# MCU089B_F280025C_Device.net
KiCad netlist of a schematic drawn in Altium Designer
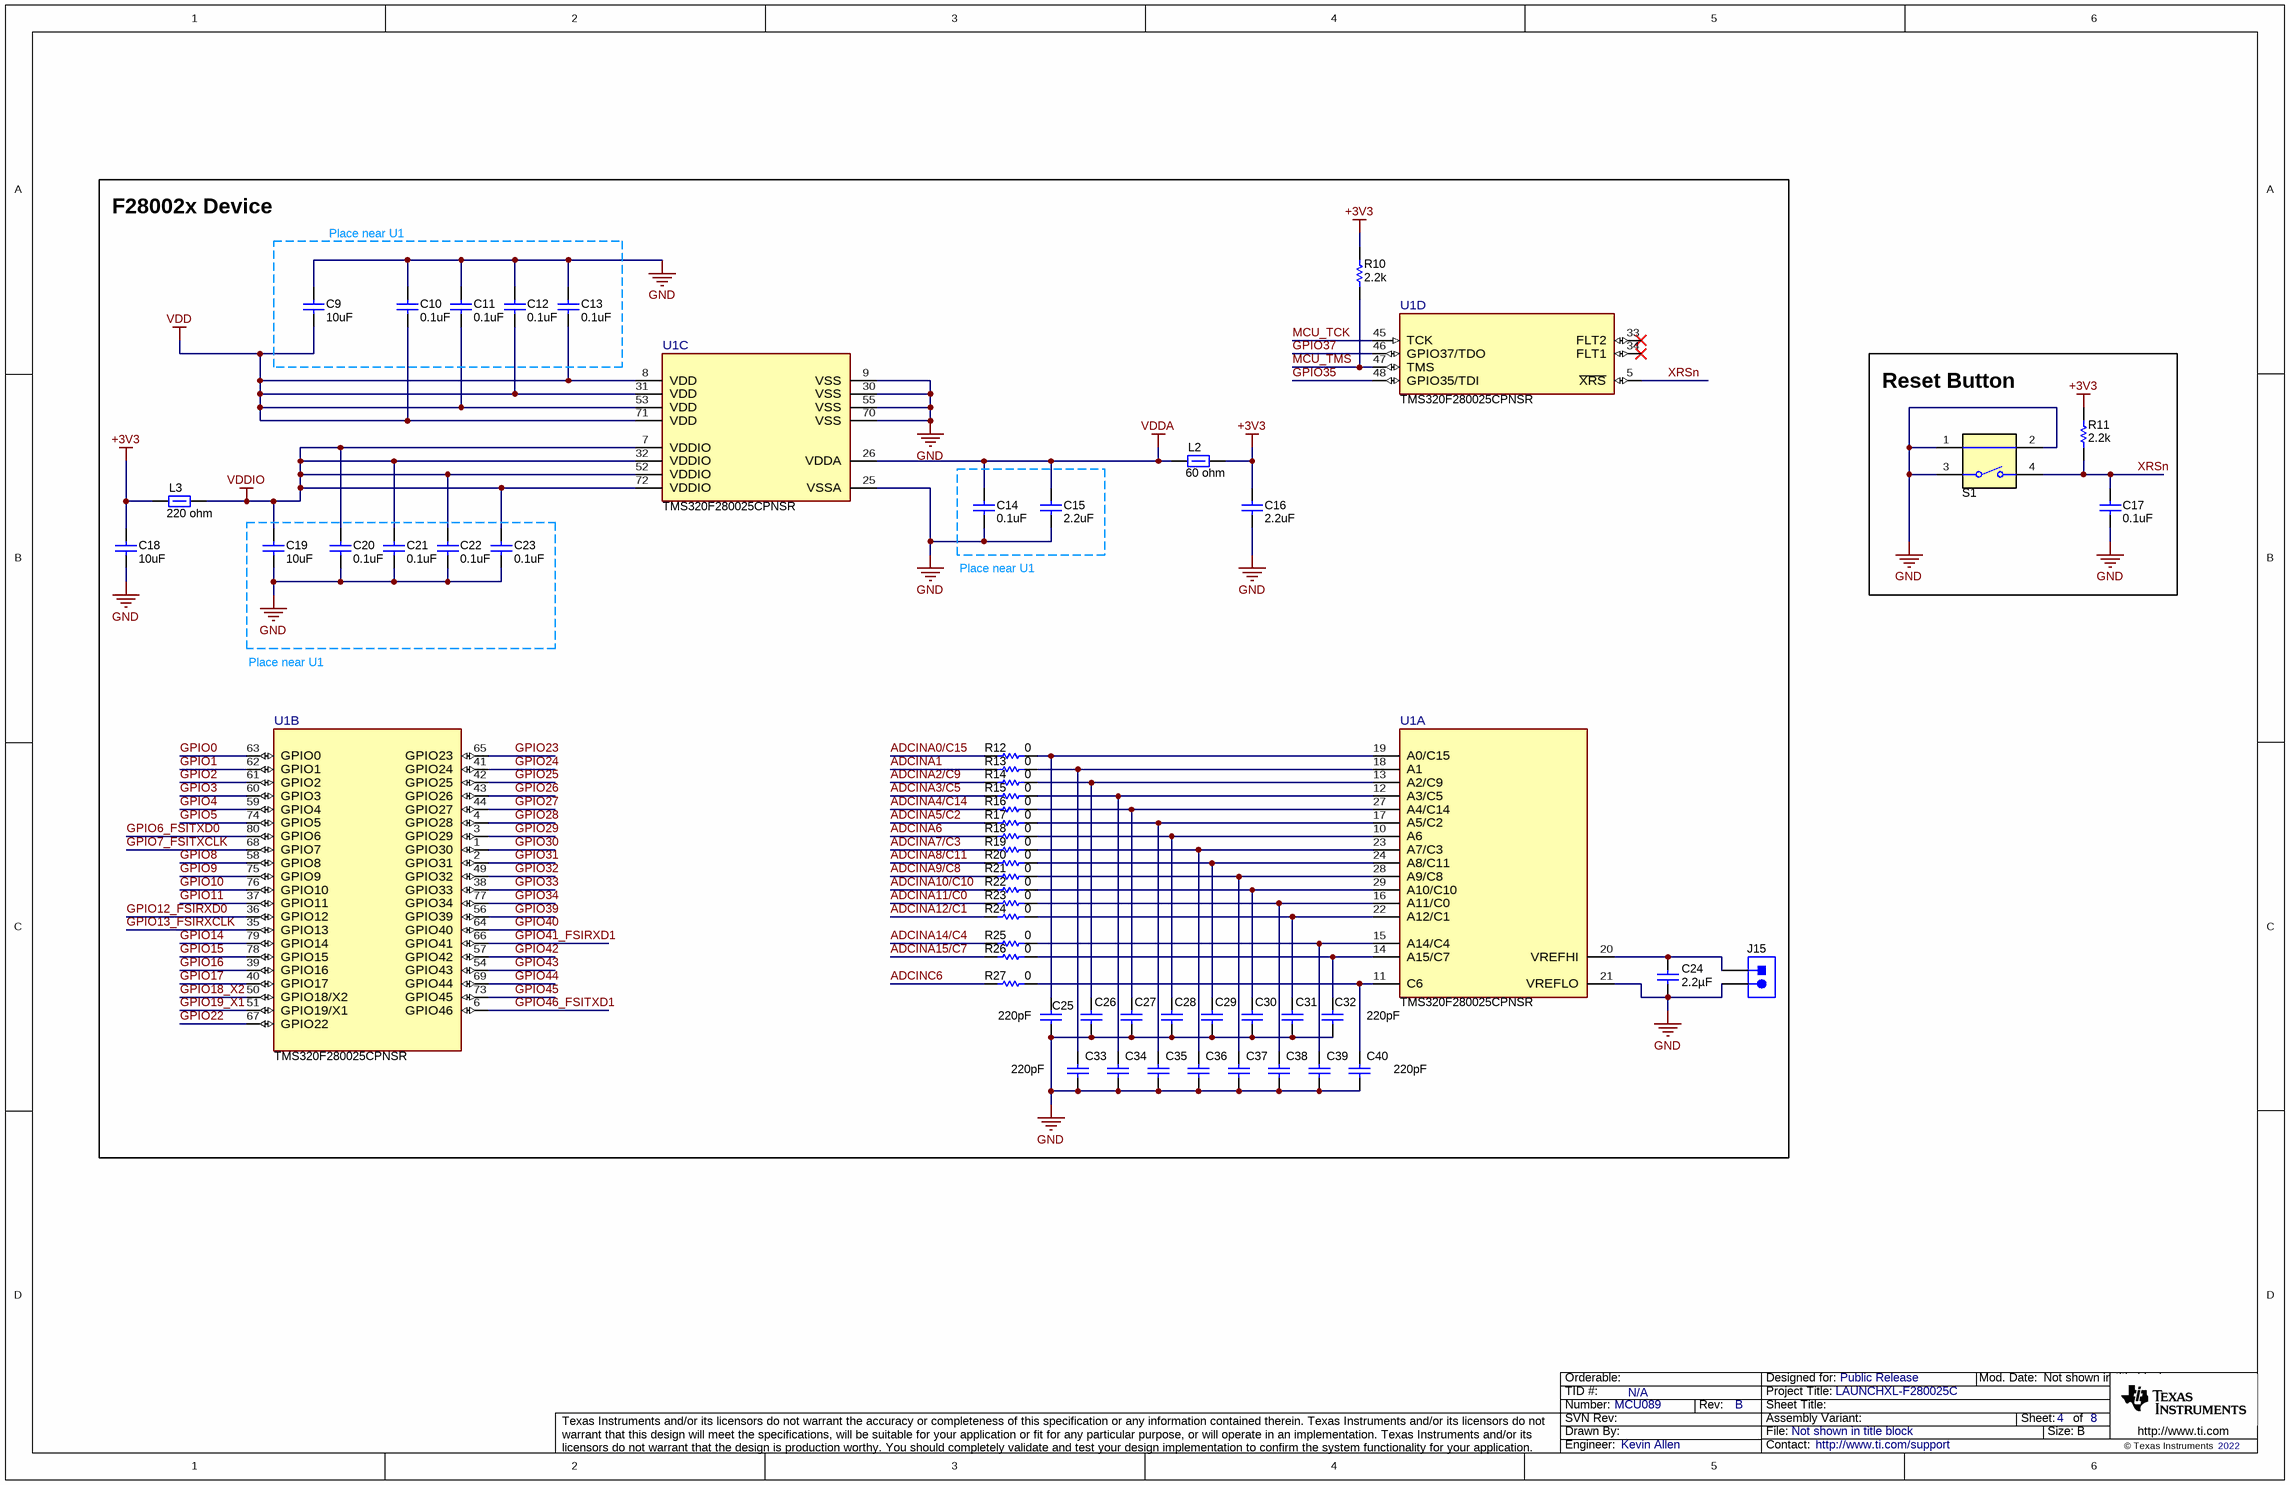
[diagram p0: MCU089B_F280025C_Device.SchDoc]

(export (version "E")
  (design (tool "Eeschema 10.0.6"))
  (components
    (comp (ref "C9")
      (value "GRM188R61A106ME69D")
      (footprint "0603")
      (description "CAP, CERM, 10 uF, 10 V, +/- 20%, X5R, 0603")
      (fields
        (field (name "VALUEDISPLAYED") "10uF")
        (field (name "MANUFACTURER") "MuRata")
        (field (name "PUBLISHER") "Texas Instruments")
      )
      (libsource (lib "Altium Vault - TI") (part "Capacitor"))
    )
    (comp (ref "C10")
      (value "GRM155R71A104KA01D")
      (footprint "0402")
      (description "CAP, CERM, 0.1 uF, 10 V, +/- 10%, X7R, 0402")
      (fields
        (field (name "VALUEDISPLAYED") "0.1uF")
        (field (name "MANUFACTURER") "MuRata")
        (field (name "PUBLISHER") "Texas Instruments")
      )
      (libsource (lib "Altium Vault - TI") (part "Capacitor"))
    )
    (comp (ref "C11")
      (value "GRM155R71A104KA01D")
      (footprint "0402")
      (description "CAP, CERM, 0.1 uF, 10 V, +/- 10%, X7R, 0402")
      (fields
        (field (name "VALUEDISPLAYED") "0.1uF")
        (field (name "MANUFACTURER") "MuRata")
        (field (name "PUBLISHER") "Texas Instruments")
      )
      (libsource (lib "Altium Vault - TI") (part "Capacitor"))
    )
    (comp (ref "C12")
      (value "GRM155R71A104KA01D")
      (footprint "0402")
      (description "CAP, CERM, 0.1 uF, 10 V, +/- 10%, X7R, 0402")
      (fields
        (field (name "VALUEDISPLAYED") "0.1uF")
        (field (name "MANUFACTURER") "MuRata")
        (field (name "PUBLISHER") "Texas Instruments")
      )
      (libsource (lib "Altium Vault - TI") (part "Capacitor"))
    )
    (comp (ref "C13")
      (value "GRM155R71A104KA01D")
      (footprint "0402")
      (description "CAP, CERM, 0.1 uF, 10 V, +/- 10%, X7R, 0402")
      (fields
        (field (name "VALUEDISPLAYED") "0.1uF")
        (field (name "MANUFACTURER") "MuRata")
        (field (name "PUBLISHER") "Texas Instruments")
      )
      (libsource (lib "Altium Vault - TI") (part "Capacitor"))
    )
    (comp (ref "C14")
      (value "GRM155R71A104KA01D")
      (footprint "0402")
      (description "CAP, CERM, 0.1 uF, 10 V, +/- 10%, X7R, 0402")
      (fields
        (field (name "VALUEDISPLAYED") "0.1uF")
        (field (name "MANUFACTURER") "MuRata")
        (field (name "PUBLISHER") "Texas Instruments")
      )
      (libsource (lib "Altium Vault - TI") (part "Capacitor"))
    )
    (comp (ref "C15")
      (value "GRM188R61A225KE34D")
      (footprint "0603")
      (description "CAP, CERM, 2.2 uF, 10 V, +/- 10%, X5R, 0603")
      (fields
        (field (name "VALUEDISPLAYED") "2.2uF")
        (field (name "MANUFACTURER") "MuRata")
        (field (name "PUBLISHER") "Texas Instruments")
      )
      (libsource (lib "Altium Vault - TI") (part "Capacitor"))
    )
    (comp (ref "C16")
      (value "GRM188R61A225KE34D")
      (footprint "0603")
      (description "CAP, CERM, 2.2 uF, 10 V, +/- 10%, X5R, 0603")
      (fields
        (field (name "VALUEDISPLAYED") "2.2uF")
        (field (name "MANUFACTURER") "MuRata")
        (field (name "PUBLISHER") "Texas Instruments")
      )
      (libsource (lib "Altium Vault - TI") (part "Capacitor"))
    )
    (comp (ref "C17")
      (value "GRM155R71A104KA01D")
      (footprint "0402")
      (description "CAP, CERM, 0.1 uF, 10 V, +/- 10%, X7R, 0402")
      (fields
        (field (name "VALUEDISPLAYED") "0.1uF")
        (field (name "MANUFACTURER") "MuRata")
        (field (name "PUBLISHER") "Texas Instruments")
      )
      (libsource (lib "Altium Vault - TI") (part "Capacitor"))
    )
    (comp (ref "C18")
      (value "GRM188R61A106ME69D")
      (footprint "0603")
      (description "CAP, CERM, 10 uF, 10 V, +/- 20%, X5R, 0603")
      (fields
        (field (name "VALUEDISPLAYED") "10uF")
        (field (name "MANUFACTURER") "MuRata")
        (field (name "PUBLISHER") "Texas Instruments")
      )
      (libsource (lib "Altium Vault - TI") (part "Capacitor"))
    )
    (comp (ref "C19")
      (value "GRM188R61A106ME69D")
      (footprint "0603")
      (description "CAP, CERM, 10 uF, 10 V, +/- 20%, X5R, 0603")
      (fields
        (field (name "VALUEDISPLAYED") "10uF")
        (field (name "MANUFACTURER") "MuRata")
        (field (name "PUBLISHER") "Texas Instruments")
      )
      (libsource (lib "Altium Vault - TI") (part "Capacitor"))
    )
    (comp (ref "C20")
      (value "GRM155R71A104KA01D")
      (footprint "0402")
      (description "CAP, CERM, 0.1 uF, 10 V, +/- 10%, X7R, 0402")
      (fields
        (field (name "VALUEDISPLAYED") "0.1uF")
        (field (name "MANUFACTURER") "MuRata")
        (field (name "PUBLISHER") "Texas Instruments")
      )
      (libsource (lib "Altium Vault - TI") (part "Capacitor"))
    )
    (comp (ref "C21")
      (value "GRM155R71A104KA01D")
      (footprint "0402")
      (description "CAP, CERM, 0.1 uF, 10 V, +/- 10%, X7R, 0402")
      (fields
        (field (name "VALUEDISPLAYED") "0.1uF")
        (field (name "MANUFACTURER") "MuRata")
        (field (name "PUBLISHER") "Texas Instruments")
      )
      (libsource (lib "Altium Vault - TI") (part "Capacitor"))
    )
    (comp (ref "C22")
      (value "GRM155R71A104KA01D")
      (footprint "0402")
      (description "CAP, CERM, 0.1 uF, 10 V, +/- 10%, X7R, 0402")
      (fields
        (field (name "VALUEDISPLAYED") "0.1uF")
        (field (name "MANUFACTURER") "MuRata")
        (field (name "PUBLISHER") "Texas Instruments")
      )
      (libsource (lib "Altium Vault - TI") (part "Capacitor"))
    )
    (comp (ref "C23")
      (value "GRM155R71A104KA01D")
      (footprint "0402")
      (description "CAP, CERM, 0.1 uF, 10 V, +/- 10%, X7R, 0402")
      (fields
        (field (name "VALUEDISPLAYED") "0.1uF")
        (field (name "MANUFACTURER") "MuRata")
        (field (name "PUBLISHER") "Texas Instruments")
      )
      (libsource (lib "Altium Vault - TI") (part "Capacitor"))
    )
    (comp (ref "C24")
      (value "GRM188R61A225KE34D")
      (footprint "0603")
      (description "CAP, CERM, 2.2 uF, 10 V, +/- 10%, X5R, 0603")
      (fields
        (field (name "MANUFACTURER") "MuRata")
        (field (name "CAP_F") "2.2µF")
        (field (name "PUBLISHER") "Texas Instruments")
      )
      (libsource (lib "Altium Vault - TI") (part "Capacitor"))
    )
    (comp (ref "C25")
      (value "C1005C0G1H221F050BA")
      (footprint "0402")
      (description "CAP, CERM, 220 pF, 50 V, +/- 1%, C0G/NP0, 0402")
      (fields
        (field (name "MANUFACTURER") "TDK")
        (field (name "CAP_F") "220pF")
        (field (name "PUBLISHER") "Texas Instruments")
      )
      (libsource (lib "Altium Vault - TI") (part "Capacitor"))
    )
    (comp (ref "C26")
      (value "C1005C0G1H221F050BA")
      (footprint "0402")
      (description "CAP, CERM, 220 pF, 50 V, +/- 1%, C0G/NP0, 0402")
      (fields (field (name "MANUFACTURER") "TDK") (field (name "PUBLISHER") "Texas Instruments"))
      (libsource (lib "Altium Vault - TI") (part "Capacitor"))
    )
    (comp (ref "C27")
      (value "C1005C0G1H221F050BA")
      (footprint "0402")
      (description "CAP, CERM, 220 pF, 50 V, +/- 1%, C0G/NP0, 0402")
      (fields (field (name "MANUFACTURER") "TDK") (field (name "PUBLISHER") "Texas Instruments"))
      (libsource (lib "Altium Vault - TI") (part "Capacitor"))
    )
    (comp (ref "C28")
      (value "C1005C0G1H221F050BA")
      (footprint "0402")
      (description "CAP, CERM, 220 pF, 50 V, +/- 1%, C0G/NP0, 0402")
      (fields (field (name "MANUFACTURER") "TDK") (field (name "PUBLISHER") "Texas Instruments"))
      (libsource (lib "Altium Vault - TI") (part "Capacitor"))
    )
    (comp (ref "C29")
      (value "C1005C0G1H221F050BA")
      (footprint "0402")
      (description "CAP, CERM, 220 pF, 50 V, +/- 1%, C0G/NP0, 0402")
      (fields (field (name "MANUFACTURER") "TDK") (field (name "PUBLISHER") "Texas Instruments"))
      (libsource (lib "Altium Vault - TI") (part "Capacitor"))
    )
    (comp (ref "C30")
      (value "C1005C0G1H221F050BA")
      (footprint "0402")
      (description "CAP, CERM, 220 pF, 50 V, +/- 1%, C0G/NP0, 0402")
      (fields (field (name "MANUFACTURER") "TDK") (field (name "PUBLISHER") "Texas Instruments"))
      (libsource (lib "Altium Vault - TI") (part "Capacitor"))
    )
    (comp (ref "C31")
      (value "C1005C0G1H221F050BA")
      (footprint "0402")
      (description "CAP, CERM, 220 pF, 50 V, +/- 1%, C0G/NP0, 0402")
      (fields (field (name "MANUFACTURER") "TDK") (field (name "PUBLISHER") "Texas Instruments"))
      (libsource (lib "Altium Vault - TI") (part "Capacitor"))
    )
    (comp (ref "C32")
      (value "C1005C0G1H221F050BA")
      (footprint "0402")
      (description "CAP, CERM, 220 pF, 50 V, +/- 1%, C0G/NP0, 0402")
      (fields
        (field (name "MANUFACTURER") "TDK")
        (field (name "CAP_F") "220pF")
        (field (name "PUBLISHER") "Texas Instruments")
      )
      (libsource (lib "Altium Vault - TI") (part "Capacitor"))
    )
    (comp (ref "C33")
      (value "C1005C0G1H221F050BA")
      (footprint "0402")
      (description "CAP, CERM, 220 pF, 50 V, +/- 1%, C0G/NP0, 0402")
      (fields
        (field (name "MANUFACTURER") "TDK")
        (field (name "CAP_F") "220pF")
        (field (name "PUBLISHER") "Texas Instruments")
      )
      (libsource (lib "Altium Vault - TI") (part "Capacitor"))
    )
    (comp (ref "C34")
      (value "C1005C0G1H221F050BA")
      (footprint "0402")
      (description "CAP, CERM, 220 pF, 50 V, +/- 1%, C0G/NP0, 0402")
      (fields (field (name "MANUFACTURER") "TDK") (field (name "PUBLISHER") "Texas Instruments"))
      (libsource (lib "Altium Vault - TI") (part "Capacitor"))
    )
    (comp (ref "C35")
      (value "C1005C0G1H221F050BA")
      (footprint "0402")
      (description "CAP, CERM, 220 pF, 50 V, +/- 1%, C0G/NP0, 0402")
      (fields (field (name "MANUFACTURER") "TDK") (field (name "PUBLISHER") "Texas Instruments"))
      (libsource (lib "Altium Vault - TI") (part "Capacitor"))
    )
    (comp (ref "C36")
      (value "C1005C0G1H221F050BA")
      (footprint "0402")
      (description "CAP, CERM, 220 pF, 50 V, +/- 1%, C0G/NP0, 0402")
      (fields (field (name "MANUFACTURER") "TDK") (field (name "PUBLISHER") "Texas Instruments"))
      (libsource (lib "Altium Vault - TI") (part "Capacitor"))
    )
    (comp (ref "C37")
      (value "C1005C0G1H221F050BA")
      (footprint "0402")
      (description "CAP, CERM, 220 pF, 50 V, +/- 1%, C0G/NP0, 0402")
      (fields (field (name "MANUFACTURER") "TDK") (field (name "PUBLISHER") "Texas Instruments"))
      (libsource (lib "Altium Vault - TI") (part "Capacitor"))
    )
    (comp (ref "C38")
      (value "C1005C0G1H221F050BA")
      (footprint "0402")
      (description "CAP, CERM, 220 pF, 50 V, +/- 1%, C0G/NP0, 0402")
      (fields (field (name "MANUFACTURER") "TDK") (field (name "PUBLISHER") "Texas Instruments"))
      (libsource (lib "Altium Vault - TI") (part "Capacitor"))
    )
    (comp (ref "C39")
      (value "C1005C0G1H221F050BA")
      (footprint "0402")
      (description "CAP, CERM, 220 pF, 50 V, +/- 1%, C0G/NP0, 0402")
      (fields (field (name "MANUFACTURER") "TDK") (field (name "PUBLISHER") "Texas Instruments"))
      (libsource (lib "Altium Vault - TI") (part "Capacitor"))
    )
    (comp (ref "C40")
      (value "C1005C0G1H221F050BA")
      (footprint "0402")
      (description "CAP, CERM, 220 pF, 50 V, +/- 1%, C0G/NP0, 0402")
      (fields
        (field (name "MANUFACTURER") "TDK")
        (field (name "CAP_F") "220pF")
        (field (name "PUBLISHER") "Texas Instruments")
      )
      (libsource (lib "Altium Vault - TI") (part "Capacitor"))
    )
    (comp (ref "J15")
      (value "61300211121")
      (footprint "WURTH_61300211121")
      (description "Header, 2.54 mm, 2x1, Gold, TH")
      (fields (field (name "MANUFACTURER") "Wurth Elektronik") (field (name "PUBLISHER") "Texas Instruments"))
      (libsource (lib "Altium Vault - TI") (part "CMP-0054794-1"))
    )
    (comp (ref "L2")
      (value "60 ohm")
      (footprint "0805_HV")
      (description "Ferrite Bead, 60 ohm @ 100 MHz, 3 A, 0805")
      (fields
        (field (name "MANUFACTURER") "Wurth Elektronik")
        (field (name "PARTNUMBER") "742792063")
        (field (name "PUBLISHER") "Texas Instruments")
      )
      (libsource (lib "Altium Vault - TI") (part "Ferrite_Bead"))
    )
    (comp (ref "L3")
      (value "742792022")
      (footprint "0805_HV")
      (description "Ferrite Bead, 220 ohm @ 100 MHz, 2 A, 0805")
      (fields
        (field (name "MANUFACTURER") "Wurth Elektronik")
        (field (name "VALUEDISPLAYED") "220 ohm")
        (field (name "PUBLISHER") "Texas Instruments")
      )
      (libsource (lib "Altium Vault - TI") (part "Ferrite_Bead"))
    )
    (comp (ref "R10")
      (value "CRCW04022K20JNED")
      (footprint "0402")
      (description "RES, 2.2 k, 5%, 0.063 W, AEC-Q200 Grade 0, 0402")
      (fields (field (name "VALUEDISPLAYED") "2.2k") (field (name "MANUFACTURER") "Vishay-Dale"))
      (libsource (lib "Altium Vault - TI") (part "Resistor"))
    )
    (comp (ref "R11")
      (value "CRCW04022K20JNED")
      (footprint "0402")
      (description "RES, 2.2 k, 5%, 0.063 W, AEC-Q200 Grade 0, 0402")
      (fields (field (name "VALUEDISPLAYED") "2.2k") (field (name "MANUFACTURER") "Vishay-Dale"))
      (libsource (lib "Altium Vault - TI") (part "Resistor"))
    )
    (comp (ref "R12")
      (value "ERJ-2GE0R00X")
      (footprint "0402")
      (description "RES, 0, 5%, 0.1 W, AEC-Q200 Grade 0, 0402")
      (fields (field (name "MANUFACTURER") "Panasonic") (field (name "VALUEDISPLAYED") "0"))
      (libsource (lib "Altium Vault - TI") (part "Resistor"))
    )
    (comp (ref "R13")
      (value "ERJ-2GE0R00X")
      (footprint "0402")
      (description "RES, 0, 5%, 0.1 W, AEC-Q200 Grade 0, 0402")
      (fields (field (name "MANUFACTURER") "Panasonic") (field (name "VALUEDISPLAYED") "0"))
      (libsource (lib "Altium Vault - TI") (part "Resistor"))
    )
    (comp (ref "R14")
      (value "ERJ-2GE0R00X")
      (footprint "0402")
      (description "RES, 0, 5%, 0.1 W, AEC-Q200 Grade 0, 0402")
      (fields (field (name "MANUFACTURER") "Panasonic") (field (name "VALUEDISPLAYED") "0"))
      (libsource (lib "Altium Vault - TI") (part "Resistor"))
    )
    (comp (ref "R15")
      (value "ERJ-2GE0R00X")
      (footprint "0402")
      (description "RES, 0, 5%, 0.1 W, AEC-Q200 Grade 0, 0402")
      (fields (field (name "MANUFACTURER") "Panasonic") (field (name "VALUEDISPLAYED") "0"))
      (libsource (lib "Altium Vault - TI") (part "Resistor"))
    )
    (comp (ref "R16")
      (value "ERJ-2GE0R00X")
      (footprint "0402")
      (description "RES, 0, 5%, 0.1 W, AEC-Q200 Grade 0, 0402")
      (fields (field (name "MANUFACTURER") "Panasonic") (field (name "VALUEDISPLAYED") "0"))
      (libsource (lib "Altium Vault - TI") (part "Resistor"))
    )
    (comp (ref "R17")
      (value "ERJ-2GE0R00X")
      (footprint "0402")
      (description "RES, 0, 5%, 0.1 W, AEC-Q200 Grade 0, 0402")
      (fields (field (name "MANUFACTURER") "Panasonic") (field (name "VALUEDISPLAYED") "0"))
      (libsource (lib "Altium Vault - TI") (part "Resistor"))
    )
    (comp (ref "R18")
      (value "ERJ-2GE0R00X")
      (footprint "0402")
      (description "RES, 0, 5%, 0.1 W, AEC-Q200 Grade 0, 0402")
      (fields (field (name "MANUFACTURER") "Panasonic") (field (name "VALUEDISPLAYED") "0"))
      (libsource (lib "Altium Vault - TI") (part "Resistor"))
    )
    (comp (ref "R19")
      (value "ERJ-2GE0R00X")
      (footprint "0402")
      (description "RES, 0, 5%, 0.1 W, AEC-Q200 Grade 0, 0402")
      (fields (field (name "MANUFACTURER") "Panasonic") (field (name "VALUEDISPLAYED") "0"))
      (libsource (lib "Altium Vault - TI") (part "Resistor"))
    )
    (comp (ref "R20")
      (value "ERJ-2GE0R00X")
      (footprint "0402")
      (description "RES, 0, 5%, 0.1 W, AEC-Q200 Grade 0, 0402")
      (fields (field (name "MANUFACTURER") "Panasonic") (field (name "VALUEDISPLAYED") "0"))
      (libsource (lib "Altium Vault - TI") (part "Resistor"))
    )
    (comp (ref "R21")
      (value "ERJ-2GE0R00X")
      (footprint "0402")
      (description "RES, 0, 5%, 0.1 W, AEC-Q200 Grade 0, 0402")
      (fields (field (name "MANUFACTURER") "Panasonic") (field (name "VALUEDISPLAYED") "0"))
      (libsource (lib "Altium Vault - TI") (part "Resistor"))
    )
    (comp (ref "R22")
      (value "ERJ-2GE0R00X")
      (footprint "0402")
      (description "RES, 0, 5%, 0.1 W, AEC-Q200 Grade 0, 0402")
      (fields (field (name "MANUFACTURER") "Panasonic") (field (name "VALUEDISPLAYED") "0"))
      (libsource (lib "Altium Vault - TI") (part "Resistor"))
    )
    (comp (ref "R23")
      (value "ERJ-2GE0R00X")
      (footprint "0402")
      (description "RES, 0, 5%, 0.1 W, AEC-Q200 Grade 0, 0402")
      (fields (field (name "MANUFACTURER") "Panasonic") (field (name "VALUEDISPLAYED") "0"))
      (libsource (lib "Altium Vault - TI") (part "Resistor"))
    )
    (comp (ref "R24")
      (value "ERJ-2GE0R00X")
      (footprint "0402")
      (description "RES, 0, 5%, 0.1 W, AEC-Q200 Grade 0, 0402")
      (fields (field (name "MANUFACTURER") "Panasonic") (field (name "VALUEDISPLAYED") "0"))
      (libsource (lib "Altium Vault - TI") (part "Resistor"))
    )
    (comp (ref "R25")
      (value "ERJ-2GE0R00X")
      (footprint "0402")
      (description "RES, 0, 5%, 0.1 W, AEC-Q200 Grade 0, 0402")
      (fields (field (name "MANUFACTURER") "Panasonic") (field (name "VALUEDISPLAYED") "0"))
      (libsource (lib "Altium Vault - TI") (part "Resistor"))
    )
    (comp (ref "R26")
      (value "ERJ-2GE0R00X")
      (footprint "0402")
      (description "RES, 0, 5%, 0.1 W, AEC-Q200 Grade 0, 0402")
      (fields (field (name "MANUFACTURER") "Panasonic") (field (name "VALUEDISPLAYED") "0"))
      (libsource (lib "Altium Vault - TI") (part "Resistor"))
    )
    (comp (ref "R27")
      (value "ERJ-2GE0R00X")
      (footprint "0402")
      (description "RES, 0, 5%, 0.1 W, AEC-Q200 Grade 0, 0402")
      (fields (field (name "MANUFACTURER") "Panasonic") (field (name "VALUEDISPLAYED") "0"))
      (libsource (lib "Altium Vault - TI") (part "Resistor"))
    )
    (comp (ref "S1")
      (value "1188E-1K2-V-TR")
      (footprint "SW_1188E")
      (description "Switch, SPST, 0.05 A, 12 VDC, SMD")
      (fields (field (name "MANUFACTURER") "Diptronics") (field (name "PUBLISHER") "Texas Instruments"))
      (libsource (lib "Altium Vault - TI") (part "SW_1188E"))
    )
    (comp (ref "U1")
      (value "TMS320F280025CPNSR")
      (footprint "PN0080A-MFG")
      (description "32-bit MCU with 100 MHz, FPU, TMU, 128-KB flash, CLB 80-LQFP -40 to 125")
      (fields
        (field (name "MANUFACTURER") "Texas Instruments")
        (field (name "PARTNUMBER") "TMS320F280025CPNSR")
      )
      (libsource (lib "Altium Vault - TI") (part "SYM-TMS320F280025CPNSR"))
    )
  )
  (nets
    (net (code "1") (name "+3V3") (class "Default")
      (node (ref "C16") (pin "1") (pinfunction "1_1") (pintype "passive"))
      (node (ref "C18") (pin "1") (pinfunction "1_1") (pintype "passive"))
      (node (ref "L2") (pin "2") (pinfunction "2_2") (pintype "passive"))
      (node (ref "L3") (pin "1") (pinfunction "1_1") (pintype "passive"))
      (node (ref "R10") (pin "2") (pinfunction "2_2") (pintype "passive"))
      (node (ref "R11") (pin "2") (pinfunction "2_2") (pintype "passive"))
    )
    (net (code "2") (name "/ADCINA0{slash}C15") (class "Default")
      (node (ref "R12") (pin "1") (pinfunction "1_1") (pintype "passive"))
    )
    (net (code "3") (name "/ADCINA1") (class "Default")
      (node (ref "R13") (pin "1") (pinfunction "1_1") (pintype "passive"))
    )
    (net (code "4") (name "/ADCINA2{slash}C9") (class "Default")
      (node (ref "R14") (pin "1") (pinfunction "1_1") (pintype "passive"))
    )
    (net (code "5") (name "/ADCINA3{slash}C5") (class "Default")
      (node (ref "R15") (pin "1") (pinfunction "1_1") (pintype "passive"))
    )
    (net (code "6") (name "/ADCINA4{slash}C14") (class "Default")
      (node (ref "R16") (pin "1") (pinfunction "1_1") (pintype "passive"))
    )
    (net (code "7") (name "/ADCINA5{slash}C2") (class "Default")
      (node (ref "R17") (pin "1") (pinfunction "1_1") (pintype "passive"))
    )
    (net (code "8") (name "/ADCINA6") (class "Default")
      (node (ref "R18") (pin "1") (pinfunction "1_1") (pintype "passive"))
    )
    (net (code "9") (name "/ADCINA7{slash}C3") (class "Default")
      (node (ref "R19") (pin "1") (pinfunction "1_1") (pintype "passive"))
    )
    (net (code "10") (name "/ADCINA8{slash}C11") (class "Default")
      (node (ref "R20") (pin "1") (pinfunction "1_1") (pintype "passive"))
    )
    (net (code "11") (name "/ADCINA9{slash}C8") (class "Default")
      (node (ref "R21") (pin "1") (pinfunction "1_1") (pintype "passive"))
    )
    (net (code "12") (name "/ADCINA10{slash}C10") (class "Default")
      (node (ref "R22") (pin "1") (pinfunction "1_1") (pintype "passive"))
    )
    (net (code "13") (name "/ADCINA11{slash}C0") (class "Default")
      (node (ref "R23") (pin "1") (pinfunction "1_1") (pintype "passive"))
    )
    (net (code "14") (name "/ADCINA12{slash}C1") (class "Default")
      (node (ref "R24") (pin "1") (pinfunction "1_1") (pintype "passive"))
    )
    (net (code "15") (name "/ADCINA14{slash}C4") (class "Default")
      (node (ref "R25") (pin "1") (pinfunction "1_1") (pintype "passive"))
    )
    (net (code "16") (name "/ADCINA15{slash}C7") (class "Default")
      (node (ref "R26") (pin "1") (pinfunction "1_1") (pintype "passive"))
    )
    (net (code "17") (name "/ADCINC6") (class "Default")
      (node (ref "R27") (pin "1") (pinfunction "1_1") (pintype "passive"))
    )
    (net (code "18") (name "/GPIO0") (class "Default")
      (node (ref "U1") (pin "63") (pinfunction "GPIO0_63") (pintype "bidirectional"))
    )
    (net (code "19") (name "/GPIO1") (class "Default")
      (node (ref "U1") (pin "62") (pinfunction "GPIO1_62") (pintype "bidirectional"))
    )
    (net (code "20") (name "/GPIO2") (class "Default")
      (node (ref "U1") (pin "61") (pinfunction "GPIO2_61") (pintype "bidirectional"))
    )
    (net (code "21") (name "/GPIO3") (class "Default")
      (node (ref "U1") (pin "60") (pinfunction "GPIO3_60") (pintype "bidirectional"))
    )
    (net (code "22") (name "/GPIO4") (class "Default")
      (node (ref "U1") (pin "59") (pinfunction "GPIO4_59") (pintype "bidirectional"))
    )
    (net (code "23") (name "/GPIO5") (class "Default")
      (node (ref "U1") (pin "74") (pinfunction "GPIO5_74") (pintype "bidirectional"))
    )
    (net (code "24") (name "/GPIO6_FSITXD0") (class "Default")
      (node (ref "U1") (pin "80") (pinfunction "GPIO6_80") (pintype "bidirectional"))
    )
    (net (code "25") (name "/GPIO7_FSITXCLK") (class "Default")
      (node (ref "U1") (pin "68") (pinfunction "GPIO7_68") (pintype "bidirectional"))
    )
    (net (code "26") (name "/GPIO8") (class "Default")
      (node (ref "U1") (pin "58") (pinfunction "GPIO8_58") (pintype "bidirectional"))
    )
    (net (code "27") (name "/GPIO9") (class "Default")
      (node (ref "U1") (pin "75") (pinfunction "GPIO9_75") (pintype "bidirectional"))
    )
    (net (code "28") (name "/GPIO10") (class "Default")
      (node (ref "U1") (pin "76") (pinfunction "GPIO10_76") (pintype "bidirectional"))
    )
    (net (code "29") (name "/GPIO11") (class "Default")
      (node (ref "U1") (pin "37") (pinfunction "GPIO11_37") (pintype "bidirectional"))
    )
    (net (code "30") (name "/GPIO12_FSIRXD0") (class "Default")
      (node (ref "U1") (pin "36") (pinfunction "GPIO12_36") (pintype "bidirectional"))
    )
    (net (code "31") (name "/GPIO13_FSIRXCLK") (class "Default")
      (node (ref "U1") (pin "35") (pinfunction "GPIO13_35") (pintype "bidirectional"))
    )
    (net (code "32") (name "/GPIO14") (class "Default")
      (node (ref "U1") (pin "79") (pinfunction "GPIO14_79") (pintype "bidirectional"))
    )
    (net (code "33") (name "/GPIO15") (class "Default")
      (node (ref "U1") (pin "78") (pinfunction "GPIO15_78") (pintype "bidirectional"))
    )
    (net (code "34") (name "/GPIO16") (class "Default")
      (node (ref "U1") (pin "39") (pinfunction "GPIO16_39") (pintype "bidirectional"))
    )
    (net (code "35") (name "/GPIO17") (class "Default")
      (node (ref "U1") (pin "40") (pinfunction "GPIO17_40") (pintype "bidirectional"))
    )
    (net (code "36") (name "/GPIO18_X2") (class "Default")
      (node (ref "U1") (pin "50") (pinfunction "GPIO18/X2_50") (pintype "bidirectional"))
    )
    (net (code "37") (name "/GPIO19_X1") (class "Default")
      (node (ref "U1") (pin "51") (pinfunction "GPIO19/X1_51") (pintype "bidirectional"))
    )
    (net (code "38") (name "/GPIO22") (class "Default")
      (node (ref "U1") (pin "67") (pinfunction "GPIO22_67") (pintype "bidirectional"))
    )
    (net (code "39") (name "/GPIO23") (class "Default")
      (node (ref "U1") (pin "65") (pinfunction "GPIO23_65") (pintype "bidirectional"))
    )
    (net (code "40") (name "/GPIO24") (class "Default")
      (node (ref "U1") (pin "41") (pinfunction "GPIO24_41") (pintype "bidirectional"))
    )
    (net (code "41") (name "/GPIO25") (class "Default")
      (node (ref "U1") (pin "42") (pinfunction "GPIO25_42") (pintype "bidirectional"))
    )
    (net (code "42") (name "/GPIO26") (class "Default")
      (node (ref "U1") (pin "43") (pinfunction "GPIO26_43") (pintype "bidirectional"))
    )
    (net (code "43") (name "/GPIO27") (class "Default")
      (node (ref "U1") (pin "44") (pinfunction "GPIO27_44") (pintype "bidirectional"))
    )
    (net (code "44") (name "/GPIO28") (class "Default")
      (node (ref "U1") (pin "4") (pinfunction "GPIO28_4") (pintype "bidirectional"))
    )
    (net (code "45") (name "/GPIO29") (class "Default")
      (node (ref "U1") (pin "3") (pinfunction "GPIO29_3") (pintype "bidirectional"))
    )
    (net (code "46") (name "/GPIO30") (class "Default")
      (node (ref "U1") (pin "1") (pinfunction "GPIO30_1") (pintype "bidirectional"))
    )
    (net (code "47") (name "/GPIO31") (class "Default")
      (node (ref "U1") (pin "2") (pinfunction "GPIO31_2") (pintype "bidirectional"))
    )
    (net (code "48") (name "/GPIO32") (class "Default")
      (node (ref "U1") (pin "49") (pinfunction "GPIO32_49") (pintype "bidirectional"))
    )
    (net (code "49") (name "/GPIO33") (class "Default")
      (node (ref "U1") (pin "38") (pinfunction "GPIO33_38") (pintype "bidirectional"))
    )
    (net (code "50") (name "/GPIO34") (class "Default")
      (node (ref "U1") (pin "77") (pinfunction "GPIO34_77") (pintype "bidirectional"))
    )
    (net (code "51") (name "/GPIO35") (class "Default")
      (node (ref "U1") (pin "48") (pinfunction "GPIO35/TDI_48") (pintype "bidirectional"))
    )
    (net (code "52") (name "/GPIO37") (class "Default")
      (node (ref "U1") (pin "46") (pinfunction "GPIO37/TDO_46") (pintype "bidirectional"))
    )
    (net (code "53") (name "/GPIO39") (class "Default")
      (node (ref "U1") (pin "56") (pinfunction "GPIO39_56") (pintype "bidirectional"))
    )
    (net (code "54") (name "/GPIO40") (class "Default")
      (node (ref "U1") (pin "64") (pinfunction "GPIO40_64") (pintype "bidirectional"))
    )
    (net (code "55") (name "/GPIO41_FSIRXD1") (class "Default")
      (node (ref "U1") (pin "66") (pinfunction "GPIO41_66") (pintype "bidirectional"))
    )
    (net (code "56") (name "/GPIO42") (class "Default")
      (node (ref "U1") (pin "57") (pinfunction "GPIO42_57") (pintype "bidirectional"))
    )
    (net (code "57") (name "/GPIO43") (class "Default")
      (node (ref "U1") (pin "54") (pinfunction "GPIO43_54") (pintype "bidirectional"))
    )
    (net (code "58") (name "/GPIO44") (class "Default")
      (node (ref "U1") (pin "69") (pinfunction "GPIO44_69") (pintype "bidirectional"))
    )
    (net (code "59") (name "/GPIO45") (class "Default")
      (node (ref "U1") (pin "73") (pinfunction "GPIO45_73") (pintype "bidirectional"))
    )
    (net (code "60") (name "/GPIO46_FSITXD1") (class "Default")
      (node (ref "U1") (pin "6") (pinfunction "GPIO46_6") (pintype "bidirectional"))
    )
    (net (code "61") (name "/MCU_TCK") (class "Default")
      (node (ref "U1") (pin "45") (pinfunction "TCK_45") (pintype "input"))
    )
    (net (code "62") (name "/MCU_TMS") (class "Default")
      (node (ref "R10") (pin "1") (pinfunction "1_1") (pintype "passive"))
      (node (ref "U1") (pin "47") (pinfunction "TMS_47") (pintype "bidirectional"))
    )
    (net (code "63") (name "/XRSn") (class "Default")
      (node (ref "C17") (pin "2") (pinfunction "2_2") (pintype "passive"))
      (node (ref "R11") (pin "1") (pinfunction "1_1") (pintype "passive"))
      (node (ref "S1") (pin "4") (pinfunction "4_4") (pintype "passive"))
      (node (ref "U1") (pin "5") (pinfunction "~{XRS}_5") (pintype "bidirectional"))
    )
    (net (code "64") (name "GND") (class "Default")
      (node (ref "C10") (pin "2") (pinfunction "2_2") (pintype "passive"))
      (node (ref "C11") (pin "2") (pinfunction "2_2") (pintype "passive"))
      (node (ref "C12") (pin "2") (pinfunction "2_2") (pintype "passive"))
      (node (ref "C13") (pin "2") (pinfunction "2_2") (pintype "passive"))
      (node (ref "C14") (pin "1") (pinfunction "1_1") (pintype "passive"))
      (node (ref "C15") (pin "2") (pinfunction "2_2") (pintype "passive"))
      (node (ref "C16") (pin "2") (pinfunction "2_2") (pintype "passive"))
      (node (ref "C17") (pin "1") (pinfunction "1_1") (pintype "passive"))
      (node (ref "C18") (pin "2") (pinfunction "2_2") (pintype "passive"))
      (node (ref "C19") (pin "2") (pinfunction "2_2") (pintype "passive"))
      (node (ref "C20") (pin "1") (pinfunction "1_1") (pintype "passive"))
      (node (ref "C21") (pin "1") (pinfunction "1_1") (pintype "passive"))
      (node (ref "C22") (pin "1") (pinfunction "1_1") (pintype "passive"))
      (node (ref "C23") (pin "1") (pinfunction "1_1") (pintype "passive"))
      (node (ref "C24") (pin "2") (pinfunction "2_2") (pintype "passive"))
      (node (ref "C25") (pin "2") (pinfunction "2_2") (pintype "passive"))
      (node (ref "C26") (pin "2") (pinfunction "2_2") (pintype "passive"))
      (node (ref "C27") (pin "2") (pinfunction "2_2") (pintype "passive"))
      (node (ref "C28") (pin "2") (pinfunction "2_2") (pintype "passive"))
      (node (ref "C29") (pin "2") (pinfunction "2_2") (pintype "passive"))
      (node (ref "C30") (pin "2") (pinfunction "2_2") (pintype "passive"))
      (node (ref "C31") (pin "2") (pinfunction "2_2") (pintype "passive"))
      (node (ref "C32") (pin "2") (pinfunction "2_2") (pintype "passive"))
      (node (ref "C33") (pin "2") (pinfunction "2_2") (pintype "passive"))
      (node (ref "C34") (pin "2") (pinfunction "2_2") (pintype "passive"))
      (node (ref "C35") (pin "2") (pinfunction "2_2") (pintype "passive"))
      (node (ref "C36") (pin "2") (pinfunction "2_2") (pintype "passive"))
      (node (ref "C37") (pin "2") (pinfunction "2_2") (pintype "passive"))
      (node (ref "C38") (pin "2") (pinfunction "2_2") (pintype "passive"))
      (node (ref "C39") (pin "2") (pinfunction "2_2") (pintype "passive"))
      (node (ref "C40") (pin "2") (pinfunction "2_2") (pintype "passive"))
      (node (ref "C9") (pin "1") (pinfunction "1_1") (pintype "passive"))
      (node (ref "J15") (pin "2") (pinfunction "2_2") (pintype "passive"))
      (node (ref "S1") (pin "1") (pinfunction "1_1") (pintype "passive"))
      (node (ref "S1") (pin "2") (pinfunction "2_2") (pintype "passive"))
      (node (ref "S1") (pin "3") (pinfunction "3_3") (pintype "passive"))
      (node (ref "U1") (pin "21") (pinfunction "VREFLO_21") (pintype "passive"))
      (node (ref "U1") (pin "25") (pinfunction "VSSA_25") (pintype "power_in"))
      (node (ref "U1") (pin "30") (pinfunction "VSS_30") (pintype "power_in"))
      (node (ref "U1") (pin "55") (pinfunction "VSS_55") (pintype "power_in"))
      (node (ref "U1") (pin "70") (pinfunction "VSS_70") (pintype "power_in"))
      (node (ref "U1") (pin "9") (pinfunction "VSS_9") (pintype "power_in"))
    )
    (net (code "65") (name "Net-(U1A-A0{slash}C15)") (class "Default")
      (node (ref "C25") (pin "1") (pinfunction "1_1") (pintype "passive"))
      (node (ref "R12") (pin "2") (pinfunction "2_2") (pintype "passive"))
      (node (ref "U1") (pin "19") (pinfunction "A0/C15_19") (pintype "passive"))
    )
    (net (code "66") (name "Net-(U1A-A1)") (class "Default")
      (node (ref "C33") (pin "1") (pinfunction "1_1") (pintype "passive"))
      (node (ref "R13") (pin "2") (pinfunction "2_2") (pintype "passive"))
      (node (ref "U1") (pin "18") (pinfunction "A1_18") (pintype "passive"))
    )
    (net (code "67") (name "Net-(U1A-A2{slash}C9)") (class "Default")
      (node (ref "C26") (pin "1") (pinfunction "1_1") (pintype "passive"))
      (node (ref "R14") (pin "2") (pinfunction "2_2") (pintype "passive"))
      (node (ref "U1") (pin "13") (pinfunction "A2/C9_13") (pintype "passive"))
    )
    (net (code "68") (name "Net-(U1A-A3{slash}C5)") (class "Default")
      (node (ref "C34") (pin "1") (pinfunction "1_1") (pintype "passive"))
      (node (ref "R15") (pin "2") (pinfunction "2_2") (pintype "passive"))
      (node (ref "U1") (pin "12") (pinfunction "A3/C5_12") (pintype "passive"))
    )
    (net (code "69") (name "Net-(U1A-A4{slash}C14)") (class "Default")
      (node (ref "C27") (pin "1") (pinfunction "1_1") (pintype "passive"))
      (node (ref "R16") (pin "2") (pinfunction "2_2") (pintype "passive"))
      (node (ref "U1") (pin "27") (pinfunction "A4/C14_27") (pintype "passive"))
    )
    (net (code "70") (name "Net-(U1A-A5{slash}C2)") (class "Default")
      (node (ref "C35") (pin "1") (pinfunction "1_1") (pintype "passive"))
      (node (ref "R17") (pin "2") (pinfunction "2_2") (pintype "passive"))
      (node (ref "U1") (pin "17") (pinfunction "A5/C2_17") (pintype "passive"))
    )
    (net (code "71") (name "Net-(U1A-A6)") (class "Default")
      (node (ref "C28") (pin "1") (pinfunction "1_1") (pintype "passive"))
      (node (ref "R18") (pin "2") (pinfunction "2_2") (pintype "passive"))
      (node (ref "U1") (pin "10") (pinfunction "A6_10") (pintype "passive"))
    )
    (net (code "72") (name "Net-(U1A-A7{slash}C3)") (class "Default")
      (node (ref "C36") (pin "1") (pinfunction "1_1") (pintype "passive"))
      (node (ref "R19") (pin "2") (pinfunction "2_2") (pintype "passive"))
      (node (ref "U1") (pin "23") (pinfunction "A7/C3_23") (pintype "passive"))
    )
    (net (code "73") (name "Net-(U1A-A8{slash}C11)") (class "Default")
      (node (ref "C29") (pin "1") (pinfunction "1_1") (pintype "passive"))
      (node (ref "R20") (pin "2") (pinfunction "2_2") (pintype "passive"))
      (node (ref "U1") (pin "24") (pinfunction "A8/C11_24") (pintype "passive"))
    )
    (net (code "74") (name "Net-(U1A-A9{slash}C8)") (class "Default")
      (node (ref "C37") (pin "1") (pinfunction "1_1") (pintype "passive"))
      (node (ref "R21") (pin "2") (pinfunction "2_2") (pintype "passive"))
      (node (ref "U1") (pin "28") (pinfunction "A9/C8_28") (pintype "passive"))
    )
    (net (code "75") (name "Net-(U1A-A10{slash}C10)") (class "Default")
      (node (ref "C30") (pin "1") (pinfunction "1_1") (pintype "passive"))
      (node (ref "R22") (pin "2") (pinfunction "2_2") (pintype "passive"))
      (node (ref "U1") (pin "29") (pinfunction "A10/C10_29") (pintype "passive"))
    )
    (net (code "76") (name "Net-(U1A-A11{slash}C0)") (class "Default")
      (node (ref "C38") (pin "1") (pinfunction "1_1") (pintype "passive"))
      (node (ref "R23") (pin "2") (pinfunction "2_2") (pintype "passive"))
      (node (ref "U1") (pin "16") (pinfunction "A11/C0_16") (pintype "passive"))
    )
    (net (code "77") (name "Net-(U1A-A12{slash}C1)") (class "Default")
      (node (ref "C31") (pin "1") (pinfunction "1_1") (pintype "passive"))
      (node (ref "R24") (pin "2") (pinfunction "2_2") (pintype "passive"))
      (node (ref "U1") (pin "22") (pinfunction "A12/C1_22") (pintype "passive"))
    )
    (net (code "78") (name "Net-(U1A-A14{slash}C4)") (class "Default")
      (node (ref "C39") (pin "1") (pinfunction "1_1") (pintype "passive"))
      (node (ref "R25") (pin "2") (pinfunction "2_2") (pintype "passive"))
      (node (ref "U1") (pin "15") (pinfunction "A14/C4_15") (pintype "passive"))
    )
    (net (code "79") (name "Net-(U1A-A15{slash}C7)") (class "Default")
      (node (ref "C32") (pin "1") (pinfunction "1_1") (pintype "passive"))
      (node (ref "R26") (pin "2") (pinfunction "2_2") (pintype "passive"))
      (node (ref "U1") (pin "14") (pinfunction "A15/C7_14") (pintype "passive"))
    )
    (net (code "80") (name "Net-(U1A-C6)") (class "Default")
      (node (ref "C40") (pin "1") (pinfunction "1_1") (pintype "passive"))
      (node (ref "R27") (pin "2") (pinfunction "2_2") (pintype "passive"))
      (node (ref "U1") (pin "11") (pinfunction "C6_11") (pintype "passive"))
    )
    (net (code "81") (name "Net-(U1A-VREFHI)") (class "Default")
      (node (ref "C24") (pin "1") (pinfunction "1_1") (pintype "passive"))
      (node (ref "J15") (pin "1") (pinfunction "1_1") (pintype "passive"))
      (node (ref "U1") (pin "20") (pinfunction "VREFHI_20") (pintype "passive"))
    )
    (net (code "82") (name "VDD") (class "Default")
      (node (ref "C10") (pin "1") (pinfunction "1_1") (pintype "passive"))
      (node (ref "C11") (pin "1") (pinfunction "1_1") (pintype "passive"))
      (node (ref "C12") (pin "1") (pinfunction "1_1") (pintype "passive"))
      (node (ref "C13") (pin "1") (pinfunction "1_1") (pintype "passive"))
      (node (ref "C9") (pin "2") (pinfunction "2_2") (pintype "passive"))
      (node (ref "U1") (pin "31") (pinfunction "VDD_31") (pintype "power_in"))
      (node (ref "U1") (pin "53") (pinfunction "VDD_53") (pintype "power_in"))
      (node (ref "U1") (pin "71") (pinfunction "VDD_71") (pintype "power_in"))
      (node (ref "U1") (pin "8") (pinfunction "VDD_8") (pintype "power_in"))
    )
    (net (code "83") (name "VDDA") (class "Default")
      (node (ref "C14") (pin "2") (pinfunction "2_2") (pintype "passive"))
      (node (ref "C15") (pin "1") (pinfunction "1_1") (pintype "passive"))
      (node (ref "L2") (pin "1") (pinfunction "1_1") (pintype "passive"))
      (node (ref "U1") (pin "26") (pinfunction "VDDA_26") (pintype "power_in"))
    )
    (net (code "84") (name "VDDIO") (class "Default")
      (node (ref "C19") (pin "1") (pinfunction "1_1") (pintype "passive"))
      (node (ref "C20") (pin "2") (pinfunction "2_2") (pintype "passive"))
      (node (ref "C21") (pin "2") (pinfunction "2_2") (pintype "passive"))
      (node (ref "C22") (pin "2") (pinfunction "2_2") (pintype "passive"))
      (node (ref "C23") (pin "2") (pinfunction "2_2") (pintype "passive"))
      (node (ref "L3") (pin "2") (pinfunction "2_2") (pintype "passive"))
      (node (ref "U1") (pin "32") (pinfunction "VDDIO_32") (pintype "power_in"))
      (node (ref "U1") (pin "52") (pinfunction "VDDIO_52") (pintype "power_in"))
      (node (ref "U1") (pin "7") (pinfunction "VDDIO_7") (pintype "power_in"))
      (node (ref "U1") (pin "72") (pinfunction "VDDIO_72") (pintype "power_in"))
    )
    (net (code "85") (name "unconnected-(U1D-FLT1-Pad34)") (class "Default")
      (node (ref "U1") (pin "34") (pinfunction "FLT1_34") (pintype "bidirectional+no_connect"))
    )
    (net (code "86") (name "unconnected-(U1D-FLT2-Pad33)") (class "Default")
      (node (ref "U1") (pin "33") (pinfunction "FLT2_33") (pintype "bidirectional+no_connect"))
    )
  )
)
